# 5V_2A_LDO_SUPPLY.net
KiCad netlist of a schematic drawn in Altium Designer
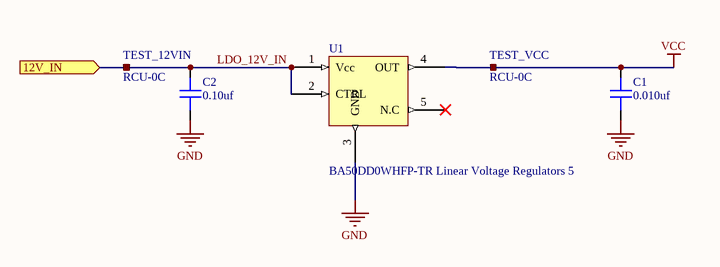
[diagram p0: 5V_2A_LDO_SUPPLY.SchDoc]

(export (version "E")
  (design (tool "Eeschema 10.0.6"))
  (components
    (comp (ref "C1")
      (value "0.010uf")
      (footprint "CAP 0603/1608")
      (fields
        (field (name "Comment") "Capacitor MLCC 0.010uf 16V CAP 0603/1608")
        (field (name "CREATED_BY") "Nick Mah")
      )
      (libsource (lib "Altium-Lib") (part "Capacitor"))
    )
    (comp (ref "C2")
      (value "0.10uf")
      (footprint "CAP 0603/1608")
      (fields
        (field (name "Comment") "Capacitor MLCC 0.10uf 16V CAP 0603/1608")
        (field (name "CREATED_BY") "Nick Mah")
      )
      (libsource (lib "Altium-Lib") (part "Capacitor"))
    )
    (comp (ref "TEST_12VIN")
      (value "RCU-0C")
      (footprint "RCU-0C")
      (libsource (lib "Altium-Lib") (part "RCU-0C"))
    )
    (comp (ref "TEST_VCC")
      (value "RCU-0C")
      (footprint "RCU-0C")
      (libsource (lib "Altium-Lib") (part "RCU-0C"))
    )
    (comp (ref "U1")
      (value "BA50DD0WHFP-TR Linear Voltage Regulators 5")
      (footprint "HRP5")
      (fields (field (name "MFRPARTNO") "BA50DD0WHFP-TR"))
      (libsource (lib "Altium-Lib") (part "BA50DD0WHFP-TR Linear Voltage Regulators 5"))
    )
  )
  (nets
    (net (code "1") (name "/LDO_12V_IN") (class "Default")
      (node (ref "C2") (pin "2") (pinfunction "2_2") (pintype "passive"))
      (node (ref "TEST_12VIN") (pin "1") (pintype "passive"))
      (node (ref "U1") (pin "1") (pinfunction "Vcc_1") (pintype "input"))
      (node (ref "U1") (pin "2") (pinfunction "CTRL_2") (pintype "input"))
    )
    (net (code "2") (name "GND") (class "Default")
      (node (ref "C1") (pin "1") (pinfunction "1_1") (pintype "passive"))
      (node (ref "C2") (pin "1") (pinfunction "1_1") (pintype "passive"))
      (node (ref "U1") (pin "3") (pinfunction "GND_3") (pintype "output"))
    )
    (net (code "3") (name "VCC") (class "Default")
      (node (ref "C1") (pin "2") (pinfunction "2_2") (pintype "passive"))
      (node (ref "TEST_VCC") (pin "1") (pintype "passive"))
      (node (ref "U1") (pin "4") (pinfunction "OUT_4") (pintype "output"))
    )
    (net (code "4") (name "unconnected-(U1-N.C-Pad5)") (class "Default")
      (node (ref "U1") (pin "5") (pinfunction "N.C_5") (pintype "output+no_connect"))
    )
  )
)
